# main.net
KiCad netlist of a schematic drawn in EAGLE
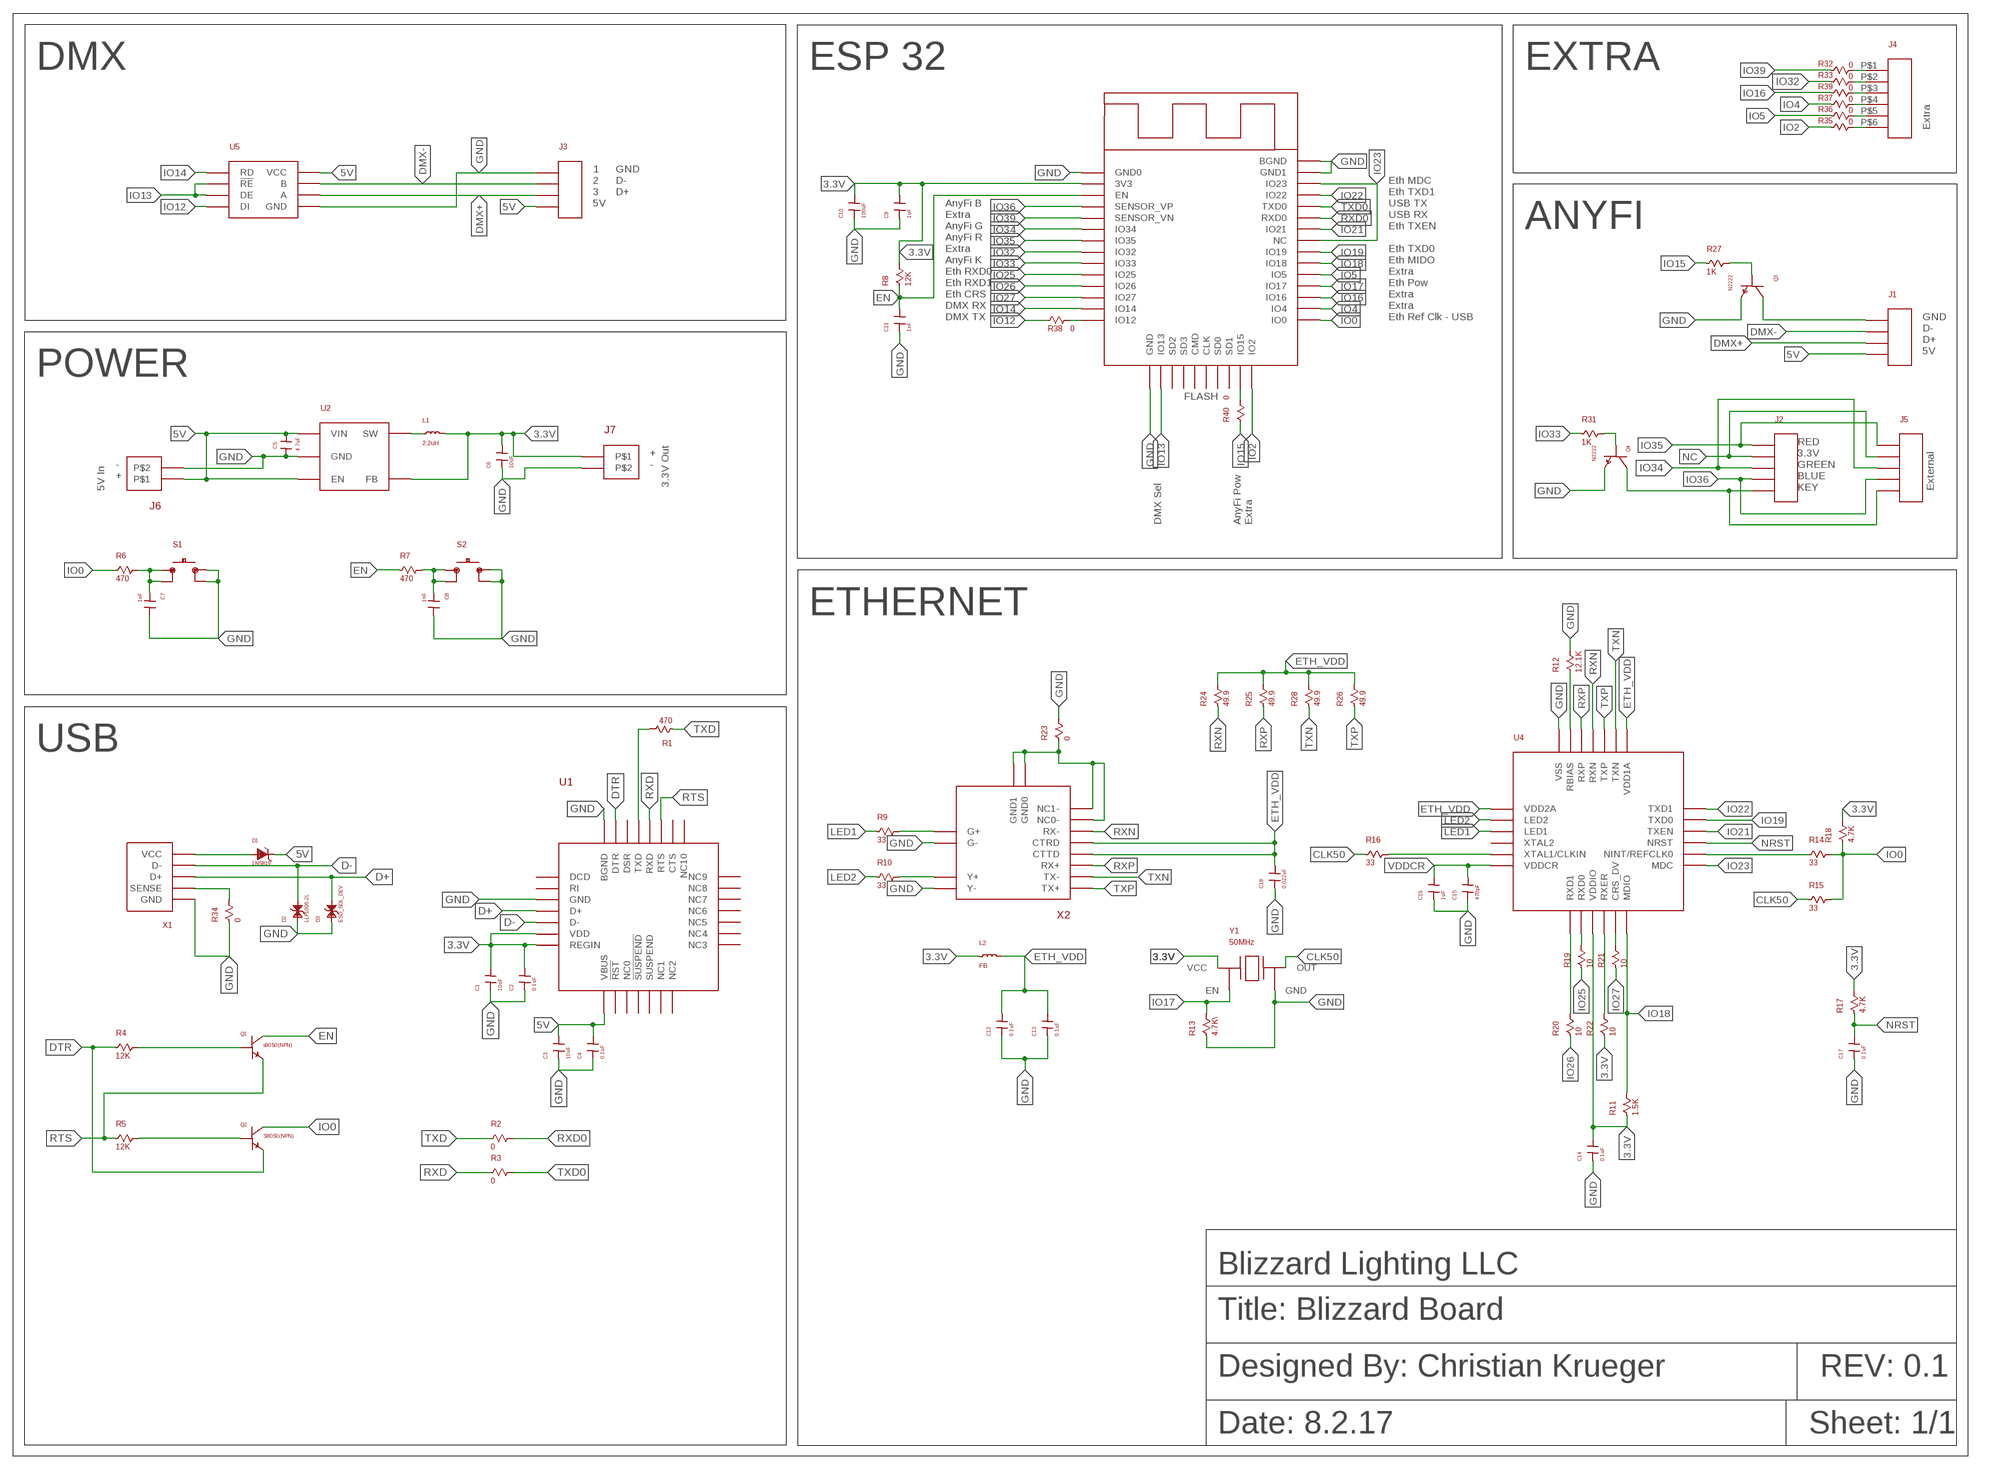
[diagram p0: schematic, sheet 1]

(export (version "E")
  (design (tool "Eeschema 10.0.6"))
  (components
    (comp (ref "C1")
      (value "10uF")
      (footprint "eagle-import:0805_PKG")
      (libsource (lib "eagle-import") (part "0805_CAP_DEV"))
    )
    (comp (ref "C2")
      (value "0.1uF")
      (footprint "eagle-import:0805_PKG")
      (libsource (lib "eagle-import") (part "0805_CAP_DEV"))
    )
    (comp (ref "C3")
      (value "10uF")
      (footprint "eagle-import:0805_PKG")
      (libsource (lib "eagle-import") (part "0805_CAP_DEV"))
    )
    (comp (ref "C4")
      (value "0.1uF")
      (footprint "eagle-import:0805_PKG")
      (libsource (lib "eagle-import") (part "0805_CAP_DEV"))
    )
    (comp (ref "C5")
      (value "4.7uF")
      (footprint "eagle-import:0805_PKG")
      (libsource (lib "eagle-import") (part "0805_CAP_DEV"))
    )
    (comp (ref "C6")
      (value "10uF")
      (footprint "eagle-import:0805_PKG")
      (libsource (lib "eagle-import") (part "0805_CAP_DEV"))
    )
    (comp (ref "C7")
      (value "1nF")
      (footprint "eagle-import:0805_PKG")
      (libsource (lib "eagle-import") (part "0805_CAP_DEV"))
    )
    (comp (ref "C8")
      (value "1nF")
      (footprint "eagle-import:0805_PKG")
      (libsource (lib "eagle-import") (part "0805_CAP_DEV"))
    )
    (comp (ref "C9")
      (value "1uF")
      (footprint "eagle-import:0805_PKG")
      (libsource (lib "eagle-import") (part "0805_CAP_DEV"))
    )
    (comp (ref "C10")
      (value "100uF")
      (footprint "eagle-import:0805_PKG")
      (libsource (lib "eagle-import") (part "0805_CAP_DEV"))
    )
    (comp (ref "C11")
      (value "1nF")
      (footprint "eagle-import:0805_PKG")
      (libsource (lib "eagle-import") (part "0805_CAP_DEV"))
    )
    (comp (ref "C12")
      (value "0.1uF")
      (footprint "eagle-import:0805_PKG")
      (libsource (lib "eagle-import") (part "0805_CAP_DEV"))
    )
    (comp (ref "C13")
      (value "0.1uF")
      (footprint "eagle-import:0805_PKG")
      (libsource (lib "eagle-import") (part "0805_CAP_DEV"))
    )
    (comp (ref "C14")
      (value "0.1uF")
      (footprint "eagle-import:0805_PKG")
      (libsource (lib "eagle-import") (part "0805_CAP_DEV"))
    )
    (comp (ref "C15")
      (value "470pF")
      (footprint "eagle-import:0805_PKG")
      (libsource (lib "eagle-import") (part "0805_CAP_DEV"))
    )
    (comp (ref "C16")
      (value "1uF")
      (footprint "eagle-import:0805_PKG")
      (libsource (lib "eagle-import") (part "0805_CAP_DEV"))
    )
    (comp (ref "C17")
      (value "0.1uF")
      (footprint "eagle-import:0805_PKG")
      (libsource (lib "eagle-import") (part "0805_CAP_DEV"))
    )
    (comp (ref "C18")
      (value "0.022uF")
      (footprint "eagle-import:0805_PKG")
      (libsource (lib "eagle-import") (part "0805_CAP_DEV"))
    )
    (comp (ref "D1")
      (value "1N5819")
      (footprint "eagle-import:ZENER_PKG")
      (libsource (lib "eagle-import") (part "ZENER_DEV"))
    )
    (comp (ref "D2")
      (value "LLP1006-2L")
      (footprint "eagle-import:ESD_SOL_PKG")
      (libsource (lib "eagle-import") (part "ESD_SOL_DEV"))
    )
    (comp (ref "D3")
      (value "ESD_SOL_DEV")
      (footprint "eagle-import:ESD_SOL_PKG")
      (libsource (lib "eagle-import") (part "ESD_SOL_DEV"))
    )
    (comp (ref "J1")
      (value "XH_4POS_DEV")
      (footprint "eagle-import:XH_4POS_PKG")
      (libsource (lib "eagle-import") (part "XH_4POS_DEV"))
    )
    (comp (ref "J2")
      (value "XH_5POS_DEV")
      (footprint "eagle-import:XH_5POS_PKG")
      (libsource (lib "eagle-import") (part "XH_5POS_DEV"))
    )
    (comp (ref "J3")
      (value "XH_4POS_DEV")
      (footprint "eagle-import:XH_4POS_PKG")
      (libsource (lib "eagle-import") (part "XH_4POS_DEV"))
    )
    (comp (ref "J4")
      (value "XH_6POS_DEV")
      (footprint "eagle-import:XH_6POS_PKG")
      (libsource (lib "eagle-import") (part "XH_6POS_DEV"))
    )
    (comp (ref "J5")
      (value "XH_5POS_DEV")
      (footprint "eagle-import:XH_5POS_PKG")
      (libsource (lib "eagle-import") (part "XH_5POS_DEV"))
    )
    (comp (ref "J6")
      (value "XH_2POS_DEV")
      (footprint "eagle-import:XH_2POS_PKG")
      (libsource (lib "eagle-import") (part "XH_2POS_DEV"))
    )
    (comp (ref "J7")
      (value "XH_2POS_DEV")
      (footprint "eagle-import:XH_2POS_PKG")
      (libsource (lib "eagle-import") (part "XH_2POS_DEV"))
    )
    (comp (ref "L1")
      (value "2.2uH")
      (footprint "eagle-import:0805_PKG")
      (libsource (lib "eagle-import") (part "0805_IND_DEV"))
    )
    (comp (ref "L2")
      (value "FB")
      (footprint "eagle-import:0805_PKG")
      (libsource (lib "eagle-import") (part "0805_IND_DEV"))
    )
    (comp (ref "Q1")
      (value "s8050(NPN)")
      (footprint "eagle-import:SOT_23_3_PKG")
      (libsource (lib "eagle-import") (part "NPN_1.5A_40V_DEV"))
    )
    (comp (ref "Q2")
      (value "S8050(NPN)")
      (footprint "eagle-import:SOT_23_3_PKG")
      (libsource (lib "eagle-import") (part "NPN_1.5A_40V_DEV"))
    )
    (comp (ref "Q3")
      (value "N2222")
      (footprint "eagle-import:SOT_23_3_PKG")
      (libsource (lib "eagle-import") (part "NPN_N2222_DEV"))
    )
    (comp (ref "Q4")
      (value "N2222")
      (footprint "eagle-import:SOT_23_3_PKG")
      (libsource (lib "eagle-import") (part "NPN_N2222_DEV"))
    )
    (comp (ref "R1")
      (value "470")
      (footprint "eagle-import:0805_PKG")
      (libsource (lib "eagle-import") (part "0805_RES_DEV"))
    )
    (comp (ref "R2")
      (value "0")
      (footprint "eagle-import:0805_PKG")
      (libsource (lib "eagle-import") (part "0805_RES_DEV"))
    )
    (comp (ref "R3")
      (value "0")
      (footprint "eagle-import:0805_PKG")
      (libsource (lib "eagle-import") (part "0805_RES_DEV"))
    )
    (comp (ref "R4")
      (value "12K")
      (footprint "eagle-import:0805_PKG")
      (libsource (lib "eagle-import") (part "0805_RES_DEV"))
    )
    (comp (ref "R5")
      (value "12K")
      (footprint "eagle-import:0805_PKG")
      (libsource (lib "eagle-import") (part "0805_RES_DEV"))
    )
    (comp (ref "R6")
      (value "470")
      (footprint "eagle-import:0805_PKG")
      (libsource (lib "eagle-import") (part "0805_RES_DEV"))
    )
    (comp (ref "R7")
      (value "470")
      (footprint "eagle-import:0805_PKG")
      (libsource (lib "eagle-import") (part "0805_RES_DEV"))
    )
    (comp (ref "R8")
      (value "12K")
      (footprint "eagle-import:0805_PKG")
      (libsource (lib "eagle-import") (part "0805_RES_DEV"))
    )
    (comp (ref "R9")
      (value "33")
      (footprint "eagle-import:0805_PKG")
      (libsource (lib "eagle-import") (part "0805_RES_DEV"))
    )
    (comp (ref "R10")
      (value "33")
      (footprint "eagle-import:0805_PKG")
      (libsource (lib "eagle-import") (part "0805_RES_DEV"))
    )
    (comp (ref "R11")
      (value "1.5K")
      (footprint "eagle-import:0805_PKG")
      (libsource (lib "eagle-import") (part "0805_RES_DEV"))
    )
    (comp (ref "R12")
      (value "12.1K")
      (footprint "eagle-import:0805_PKG")
      (libsource (lib "eagle-import") (part "0805_RES_DEV"))
    )
    (comp (ref "R13")
      (value "4.7K\\")
      (footprint "eagle-import:0805_PKG")
      (libsource (lib "eagle-import") (part "0805_RES_DEV"))
    )
    (comp (ref "R14")
      (value "33")
      (footprint "eagle-import:0805_PKG")
      (libsource (lib "eagle-import") (part "0805_RES_DEV"))
    )
    (comp (ref "R15")
      (value "33")
      (footprint "eagle-import:0805_PKG")
      (libsource (lib "eagle-import") (part "0805_RES_DEV"))
    )
    (comp (ref "R16")
      (value "33")
      (footprint "eagle-import:0805_PKG")
      (libsource (lib "eagle-import") (part "0805_RES_DEV"))
    )
    (comp (ref "R17")
      (value "4.7K")
      (footprint "eagle-import:0805_PKG")
      (libsource (lib "eagle-import") (part "0805_RES_DEV"))
    )
    (comp (ref "R18")
      (value "4.7K")
      (footprint "eagle-import:0805_PKG")
      (libsource (lib "eagle-import") (part "0805_RES_DEV"))
    )
    (comp (ref "R19")
      (value "10")
      (footprint "eagle-import:0805_PKG")
      (libsource (lib "eagle-import") (part "0805_RES_DEV"))
    )
    (comp (ref "R20")
      (value "10")
      (footprint "eagle-import:0805_PKG")
      (libsource (lib "eagle-import") (part "0805_RES_DEV"))
    )
    (comp (ref "R21")
      (value "10")
      (footprint "eagle-import:0805_PKG")
      (libsource (lib "eagle-import") (part "0805_RES_DEV"))
    )
    (comp (ref "R22")
      (value "10")
      (footprint "eagle-import:0805_PKG")
      (libsource (lib "eagle-import") (part "0805_RES_DEV"))
    )
    (comp (ref "R23")
      (value "0")
      (footprint "eagle-import:0805_PKG")
      (libsource (lib "eagle-import") (part "0805_RES_DEV"))
    )
    (comp (ref "R24")
      (value "49.9")
      (footprint "eagle-import:0805_PKG")
      (libsource (lib "eagle-import") (part "0805_RES_DEV"))
    )
    (comp (ref "R25")
      (value "49.9")
      (footprint "eagle-import:0805_PKG")
      (libsource (lib "eagle-import") (part "0805_RES_DEV"))
    )
    (comp (ref "R26")
      (value "49.9")
      (footprint "eagle-import:0805_PKG")
      (libsource (lib "eagle-import") (part "0805_RES_DEV"))
    )
    (comp (ref "R27")
      (value "1K")
      (footprint "eagle-import:0805_PKG")
      (libsource (lib "eagle-import") (part "0805_RES_DEV"))
    )
    (comp (ref "R28")
      (value "49.9")
      (footprint "eagle-import:0805_PKG")
      (libsource (lib "eagle-import") (part "0805_RES_DEV"))
    )
    (comp (ref "R31")
      (value "1K")
      (footprint "eagle-import:0805_PKG")
      (libsource (lib "eagle-import") (part "0805_RES_DEV"))
    )
    (comp (ref "R32")
      (value "0")
      (footprint "eagle-import:0805_PKG")
      (libsource (lib "eagle-import") (part "0805_RES_DEV"))
    )
    (comp (ref "R33")
      (value "0")
      (footprint "eagle-import:0805_PKG")
      (libsource (lib "eagle-import") (part "0805_RES_DEV"))
    )
    (comp (ref "R34")
      (value "0")
      (footprint "eagle-import:0805_PKG")
      (libsource (lib "eagle-import") (part "0805_RES_DEV"))
    )
    (comp (ref "R35")
      (value "0")
      (footprint "eagle-import:0805_PKG")
      (libsource (lib "eagle-import") (part "0805_RES_DEV"))
    )
    (comp (ref "R36")
      (value "0")
      (footprint "eagle-import:0805_PKG")
      (libsource (lib "eagle-import") (part "0805_RES_DEV"))
    )
    (comp (ref "R37")
      (value "0")
      (footprint "eagle-import:0805_PKG")
      (libsource (lib "eagle-import") (part "0805_RES_DEV"))
    )
    (comp (ref "R38")
      (value "0")
      (footprint "eagle-import:0805_PKG")
      (libsource (lib "eagle-import") (part "0805_RES_DEV"))
    )
    (comp (ref "R39")
      (value "0")
      (footprint "eagle-import:0805_PKG")
      (libsource (lib "eagle-import") (part "0805_RES_DEV"))
    )
    (comp (ref "R40")
      (value "0")
      (footprint "eagle-import:0805_PKG")
      (libsource (lib "eagle-import") (part "0805_RES_DEV"))
    )
    (comp (ref "S1")
      (value "TACTILE_PB_DEV")
      (footprint "eagle-import:TACKTILE_PB_PKG")
      (libsource (lib "eagle-import") (part "TACTILE_PB_DEV"))
    )
    (comp (ref "S2")
      (value "TACTILE_PB_DEV")
      (footprint "eagle-import:TACKTILE_PB_PKG")
      (libsource (lib "eagle-import") (part "TACTILE_PB_DEV"))
    )
    (comp (ref "U1")
      (value "USB_TO_UART_DEV")
      (footprint "eagle-import:QFN_28_PKG")
      (libsource (lib "eagle-import") (part "USB_TO_UART_DEV"))
    )
    (comp (ref "U2")
      (value "BUCK_CONVERTER_DEV")
      (footprint "eagle-import:SOT_23_PKG")
      (libsource (lib "eagle-import") (part "BUCK_CONVERTER_DEV"))
    )
    (comp (ref "U3")
      (value "ESP_WROOM_32_DEV")
      (footprint "eagle-import:ESP_WROOM_32_PKG")
      (libsource (lib "eagle-import") (part "ESP_WROOM_32_DEV"))
    )
    (comp (ref "U4")
      (value "LAN8720_DEV")
      (footprint "eagle-import:QFN_24_PKG")
      (libsource (lib "eagle-import") (part "LAN8720_DEV"))
    )
    (comp (ref "U5")
      (value "MAX_485_DEV")
      (footprint "eagle-import:MAX_485_PKG")
      (libsource (lib "eagle-import") (part "MAX_485_DEV"))
    )
    (comp (ref "X1")
      (value "USB_CONN_DEV")
      (footprint "eagle-import:USB_CONN_PKG")
      (libsource (lib "eagle-import") (part "USB_CONN_DEV"))
    )
    (comp (ref "X2")
      (value "ETHERNET_DEV")
      (footprint "eagle-import:ETHERNET_PKG")
      (libsource (lib "eagle-import") (part "ETHERNET_DEV"))
    )
    (comp (ref "Y1")
      (value "50MHz")
      (footprint "eagle-import:OSC_PKG")
      (libsource (lib "eagle-import") (part "OSC_DEV"))
    )
  )
  (nets
    (net (code "1") (name "3.3V") (class "Default")
      (node (ref "C1") (pin "P$2") (pinfunction "P$2_P$2") (pintype "bidirectional"))
      (node (ref "C10") (pin "P$2") (pinfunction "P$2_P$2") (pintype "bidirectional"))
      (node (ref "C14") (pin "P$2") (pinfunction "P$2_P$2") (pintype "bidirectional"))
      (node (ref "C2") (pin "P$2") (pinfunction "P$2_P$2") (pintype "bidirectional"))
      (node (ref "C6") (pin "P$2") (pinfunction "P$2_P$2") (pintype "bidirectional"))
      (node (ref "C9") (pin "P$2") (pinfunction "P$2_P$2") (pintype "bidirectional"))
      (node (ref "J7") (pin "P$1") (pinfunction "P$1_P$1") (pintype "bidirectional"))
      (node (ref "L1") (pin "P$2") (pinfunction "P$2_P$2") (pintype "bidirectional"))
      (node (ref "L2") (pin "P$1") (pinfunction "P$1_P$1") (pintype "bidirectional"))
      (node (ref "R11") (pin "P$1") (pinfunction "P$1_P$1") (pintype "bidirectional"))
      (node (ref "R17") (pin "P$2") (pinfunction "P$2_P$2") (pintype "bidirectional"))
      (node (ref "R18") (pin "P$2") (pinfunction "P$2_P$2") (pintype "bidirectional"))
      (node (ref "R22") (pin "P$1") (pinfunction "P$1_P$1") (pintype "bidirectional"))
      (node (ref "R8") (pin "P$2") (pinfunction "P$2_P$2") (pintype "bidirectional"))
      (node (ref "U1") (pin "REGIN") (pinfunction "REGIN_REGIN") (pintype "bidirectional"))
      (node (ref "U1") (pin "VDD") (pinfunction "VDD_VDD") (pintype "bidirectional"))
      (node (ref "U2") (pin "4") (pinfunction "FB_4") (pintype "bidirectional"))
      (node (ref "U3") (pin "3V3") (pinfunction "3V3_3V3") (pintype "bidirectional"))
      (node (ref "U4") (pin "9") (pinfunction "VDDIO_9") (pintype "bidirectional"))
      (node (ref "Y1") (pin "4") (pinfunction "VCC_4") (pintype "bidirectional"))
    )
    (net (code "2") (name "5V") (class "Default")
      (node (ref "C3") (pin "P$2") (pinfunction "P$2_P$2") (pintype "bidirectional"))
      (node (ref "C4") (pin "P$2") (pinfunction "P$2_P$2") (pintype "bidirectional"))
      (node (ref "C5") (pin "P$2") (pinfunction "P$2_P$2") (pintype "bidirectional"))
      (node (ref "D1") (pin "P$2") (pinfunction "P$2_P$2") (pintype "bidirectional"))
      (node (ref "J1") (pin "P$4") (pinfunction "P$4_P$4") (pintype "bidirectional"))
      (node (ref "J3") (pin "P$4") (pinfunction "P$4_P$4") (pintype "bidirectional"))
      (node (ref "J6") (pin "P$1") (pinfunction "P$1_P$1") (pintype "bidirectional"))
      (node (ref "U1") (pin "VBUS") (pinfunction "VBUS_VBUS") (pintype "bidirectional"))
      (node (ref "U2") (pin "1") (pinfunction "VIN_1") (pintype "bidirectional"))
      (node (ref "U2") (pin "3") (pinfunction "EN_3") (pintype "bidirectional"))
      (node (ref "U5") (pin "P$8") (pinfunction "VCC_P$8") (pintype "bidirectional"))
    )
    (net (code "3") (name "CLK50") (class "Default")
      (node (ref "R15") (pin "P$1") (pinfunction "P$1_P$1") (pintype "bidirectional"))
      (node (ref "R16") (pin "P$1") (pinfunction "P$1_P$1") (pintype "bidirectional"))
      (node (ref "Y1") (pin "3") (pinfunction "OUT_3") (pintype "bidirectional"))
    )
    (net (code "4") (name "D+") (class "Default")
      (node (ref "D3") (pin "P$2") (pinfunction "P$2_P$2") (pintype "bidirectional"))
      (node (ref "U1") (pin "D+") (pinfunction "D+_D+") (pintype "bidirectional"))
      (node (ref "X1") (pin "PIN3") (pinfunction "D+_PIN3") (pintype "bidirectional"))
    )
    (net (code "5") (name "D-") (class "Default")
      (node (ref "D2") (pin "P$2") (pinfunction "P$2_P$2") (pintype "bidirectional"))
      (node (ref "U1") (pin "D-") (pinfunction "D-_D-") (pintype "bidirectional"))
      (node (ref "X1") (pin "PIN2") (pinfunction "D-_PIN2") (pintype "bidirectional"))
    )
    (net (code "6") (name "DMX+") (class "Default")
      (node (ref "J1") (pin "P$3") (pinfunction "P$3_P$3") (pintype "bidirectional"))
      (node (ref "J3") (pin "P$3") (pinfunction "P$3_P$3") (pintype "bidirectional"))
      (node (ref "U5") (pin "P$6") (pinfunction "A_P$6") (pintype "bidirectional"))
    )
    (net (code "7") (name "DMX-") (class "Default")
      (node (ref "J1") (pin "P$2") (pinfunction "P$2_P$2") (pintype "bidirectional"))
      (node (ref "J3") (pin "P$2") (pinfunction "P$2_P$2") (pintype "bidirectional"))
      (node (ref "U5") (pin "P$7") (pinfunction "B_P$7") (pintype "bidirectional"))
    )
    (net (code "8") (name "DTR") (class "Default")
      (node (ref "Q2") (pin "P$2") (pinfunction "E_P$2") (pintype "bidirectional"))
      (node (ref "R4") (pin "P$1") (pinfunction "P$1_P$1") (pintype "bidirectional"))
      (node (ref "U1") (pin "DTR") (pinfunction "DTR_DTR") (pintype "bidirectional"))
    )
    (net (code "9") (name "EN") (class "Default")
      (node (ref "C11") (pin "P$2") (pinfunction "P$2_P$2") (pintype "bidirectional"))
      (node (ref "Q1") (pin "P$3") (pinfunction "C_P$3") (pintype "bidirectional"))
      (node (ref "R7") (pin "P$1") (pinfunction "P$1_P$1") (pintype "bidirectional"))
      (node (ref "R8") (pin "P$1") (pinfunction "P$1_P$1") (pintype "bidirectional"))
      (node (ref "U3") (pin "EN") (pinfunction "EN_EN") (pintype "bidirectional"))
    )
    (net (code "10") (name "ETH_VDD") (class "Default")
      (node (ref "C12") (pin "P$2") (pinfunction "P$2_P$2") (pintype "bidirectional"))
      (node (ref "C13") (pin "P$2") (pinfunction "P$2_P$2") (pintype "bidirectional"))
      (node (ref "C18") (pin "P$2") (pinfunction "P$2_P$2") (pintype "bidirectional"))
      (node (ref "L2") (pin "P$2") (pinfunction "P$2_P$2") (pintype "bidirectional"))
      (node (ref "R24") (pin "P$2") (pinfunction "P$2_P$2") (pintype "bidirectional"))
      (node (ref "R25") (pin "P$2") (pinfunction "P$2_P$2") (pintype "bidirectional"))
      (node (ref "R26") (pin "P$2") (pinfunction "P$2_P$2") (pintype "bidirectional"))
      (node (ref "R28") (pin "P$2") (pinfunction "P$2_P$2") (pintype "bidirectional"))
      (node (ref "U4") (pin "1") (pinfunction "VDD2A_1") (pintype "bidirectional"))
      (node (ref "U4") (pin "19") (pinfunction "VDD1A_19") (pintype "bidirectional"))
      (node (ref "X2") (pin "4") (pinfunction "CTTD_4") (pintype "bidirectional"))
      (node (ref "X2") (pin "5") (pinfunction "CTRD_5") (pintype "bidirectional"))
    )
    (net (code "11") (name "GND") (class "Default")
      (node (ref "C1") (pin "P$1") (pinfunction "P$1_P$1") (pintype "bidirectional"))
      (node (ref "C10") (pin "P$1") (pinfunction "P$1_P$1") (pintype "bidirectional"))
      (node (ref "C11") (pin "P$1") (pinfunction "P$1_P$1") (pintype "bidirectional"))
      (node (ref "C12") (pin "P$1") (pinfunction "P$1_P$1") (pintype "bidirectional"))
      (node (ref "C13") (pin "P$1") (pinfunction "P$1_P$1") (pintype "bidirectional"))
      (node (ref "C14") (pin "P$1") (pinfunction "P$1_P$1") (pintype "bidirectional"))
      (node (ref "C15") (pin "P$1") (pinfunction "P$1_P$1") (pintype "bidirectional"))
      (node (ref "C16") (pin "P$1") (pinfunction "P$1_P$1") (pintype "bidirectional"))
      (node (ref "C17") (pin "P$1") (pinfunction "P$1_P$1") (pintype "bidirectional"))
      (node (ref "C18") (pin "P$1") (pinfunction "P$1_P$1") (pintype "bidirectional"))
      (node (ref "C2") (pin "P$1") (pinfunction "P$1_P$1") (pintype "bidirectional"))
      (node (ref "C3") (pin "P$1") (pinfunction "P$1_P$1") (pintype "bidirectional"))
      (node (ref "C4") (pin "P$1") (pinfunction "P$1_P$1") (pintype "bidirectional"))
      (node (ref "C5") (pin "P$1") (pinfunction "P$1_P$1") (pintype "bidirectional"))
      (node (ref "C6") (pin "P$1") (pinfunction "P$1_P$1") (pintype "bidirectional"))
      (node (ref "C7") (pin "P$2") (pinfunction "P$2_P$2") (pintype "bidirectional"))
      (node (ref "C8") (pin "P$2") (pinfunction "P$2_P$2") (pintype "bidirectional"))
      (node (ref "C9") (pin "P$1") (pinfunction "P$1_P$1") (pintype "bidirectional"))
      (node (ref "D2") (pin "P$1") (pinfunction "P$1_P$1") (pintype "bidirectional"))
      (node (ref "D3") (pin "P$1") (pinfunction "P$1_P$1") (pintype "bidirectional"))
      (node (ref "J3") (pin "P$1") (pinfunction "P$1_P$1") (pintype "bidirectional"))
      (node (ref "J6") (pin "P$2") (pinfunction "P$2_P$2") (pintype "bidirectional"))
      (node (ref "J7") (pin "P$2") (pinfunction "P$2_P$2") (pintype "bidirectional"))
      (node (ref "Q3") (pin "P$2") (pinfunction "E_P$2") (pintype "bidirectional"))
      (node (ref "Q4") (pin "P$2") (pinfunction "E_P$2") (pintype "bidirectional"))
      (node (ref "R12") (pin "P$2") (pinfunction "P$2_P$2") (pintype "bidirectional"))
      (node (ref "R13") (pin "P$1") (pinfunction "P$1_P$1") (pintype "bidirectional"))
      (node (ref "R23") (pin "P$2") (pinfunction "P$2_P$2") (pintype "bidirectional"))
      (node (ref "R34") (pin "P$2") (pinfunction "P$2_P$2") (pintype "bidirectional"))
      (node (ref "S1") (pin "3") (pinfunction "3_3") (pintype "bidirectional"))
      (node (ref "S1") (pin "4") (pinfunction "4_4") (pintype "bidirectional"))
      (node (ref "S2") (pin "3") (pinfunction "3_3") (pintype "bidirectional"))
      (node (ref "S2") (pin "4") (pinfunction "4_4") (pintype "bidirectional"))
      (node (ref "U1") (pin "BGND") (pinfunction "BGND_BGND") (pintype "bidirectional"))
      (node (ref "U1") (pin "GND") (pinfunction "GND_GND") (pintype "bidirectional"))
      (node (ref "U2") (pin "2") (pinfunction "GND_2") (pintype "bidirectional"))
      (node (ref "U3") (pin "BGND") (pinfunction "BGND_BGND") (pintype "bidirectional"))
      (node (ref "U3") (pin "GND0") (pinfunction "GND_GND0") (pintype "bidirectional"))
      (node (ref "U3") (pin "GND1") (pinfunction "GND0_GND1") (pintype "bidirectional"))
      (node (ref "U3") (pin "GND2") (pinfunction "GND1_GND2") (pintype "bidirectional"))
      (node (ref "U4") (pin "BGND") (pinfunction "VSS_BGND") (pintype "bidirectional"))
      (node (ref "U5") (pin "P$5") (pinfunction "GND_P$5") (pintype "bidirectional"))
      (node (ref "X1") (pin "PIN4") (pinfunction "SENSE_PIN4") (pintype "bidirectional"))
      (node (ref "X2") (pin "G-") (pinfunction "G-_G-") (pintype "bidirectional"))
      (node (ref "X2") (pin "Y-") (pinfunction "Y-_Y-") (pintype "bidirectional"))
      (node (ref "Y1") (pin "2") (pinfunction "GND_2") (pintype "bidirectional"))
    )
    (net (code "12") (name "IO0") (class "Default")
      (node (ref "Q2") (pin "P$3") (pinfunction "C_P$3") (pintype "bidirectional"))
      (node (ref "R14") (pin "P$2") (pinfunction "P$2_P$2") (pintype "bidirectional"))
      (node (ref "R15") (pin "P$2") (pinfunction "P$2_P$2") (pintype "bidirectional"))
      (node (ref "R18") (pin "P$1") (pinfunction "P$1_P$1") (pintype "bidirectional"))
      (node (ref "R6") (pin "P$1") (pinfunction "P$1_P$1") (pintype "bidirectional"))
      (node (ref "U3") (pin "IO0") (pinfunction "IO0_IO0") (pintype "bidirectional"))
    )
    (net (code "13") (name "IO2") (class "Default")
      (node (ref "R35") (pin "P$1") (pinfunction "P$1_P$1") (pintype "bidirectional"))
      (node (ref "U3") (pin "IO2") (pinfunction "IO2_IO2") (pintype "bidirectional"))
    )
    (net (code "14") (name "IO4") (class "Default")
      (node (ref "R37") (pin "P$1") (pinfunction "P$1_P$1") (pintype "bidirectional"))
      (node (ref "U3") (pin "IO4") (pinfunction "IO4_IO4") (pintype "bidirectional"))
    )
    (net (code "15") (name "IO5") (class "Default")
      (node (ref "R36") (pin "P$1") (pinfunction "P$1_P$1") (pintype "bidirectional"))
      (node (ref "U3") (pin "IO5") (pinfunction "IO5_IO5") (pintype "bidirectional"))
    )
    (net (code "16") (name "IO12") (class "Default")
      (node (ref "R38") (pin "P$1") (pinfunction "P$1_P$1") (pintype "bidirectional"))
      (node (ref "U5") (pin "P$4") (pinfunction "DI_P$4") (pintype "bidirectional"))
    )
    (net (code "17") (name "IO13") (class "Default")
      (node (ref "U3") (pin "IO13") (pinfunction "IO13_IO13") (pintype "bidirectional"))
      (node (ref "U5") (pin "P$2") (pinfunction "~{RE}_P$2") (pintype "bidirectional"))
      (node (ref "U5") (pin "P$3") (pinfunction "DE_P$3") (pintype "bidirectional"))
    )
    (net (code "18") (name "IO14") (class "Default")
      (node (ref "U3") (pin "IO14") (pinfunction "IO14_IO14") (pintype "bidirectional"))
      (node (ref "U5") (pin "P$1") (pinfunction "RD_P$1") (pintype "bidirectional"))
    )
    (net (code "19") (name "IO15") (class "Default")
      (node (ref "R27") (pin "P$1") (pinfunction "P$1_P$1") (pintype "bidirectional"))
      (node (ref "R40") (pin "P$1") (pinfunction "P$1_P$1") (pintype "bidirectional"))
    )
    (net (code "20") (name "IO16") (class "Default")
      (node (ref "R39") (pin "P$1") (pinfunction "P$1_P$1") (pintype "bidirectional"))
      (node (ref "U3") (pin "IO16") (pinfunction "IO16_IO16") (pintype "bidirectional"))
    )
    (net (code "21") (name "IO17") (class "Default")
      (node (ref "R13") (pin "P$2") (pinfunction "P$2_P$2") (pintype "bidirectional"))
      (node (ref "U3") (pin "IO17") (pinfunction "IO17_IO17") (pintype "bidirectional"))
      (node (ref "Y1") (pin "1") (pinfunction "EN_1") (pintype "bidirectional"))
    )
    (net (code "22") (name "IO18") (class "Default")
      (node (ref "R11") (pin "P$2") (pinfunction "P$2_P$2") (pintype "bidirectional"))
      (node (ref "U3") (pin "IO18") (pinfunction "IO18_IO18") (pintype "bidirectional"))
      (node (ref "U4") (pin "12") (pinfunction "MDIO_12") (pintype "bidirectional"))
    )
    (net (code "23") (name "IO19") (class "Default")
      (node (ref "U3") (pin "IO19") (pinfunction "IO19_IO19") (pintype "bidirectional"))
      (node (ref "U4") (pin "17") (pinfunction "TXD0_17") (pintype "bidirectional"))
    )
    (net (code "24") (name "IO21") (class "Default")
      (node (ref "U3") (pin "IO21") (pinfunction "IO21_IO21") (pintype "bidirectional"))
      (node (ref "U4") (pin "16") (pinfunction "TXEN_16") (pintype "bidirectional"))
    )
    (net (code "25") (name "IO22") (class "Default")
      (node (ref "U3") (pin "IO22") (pinfunction "IO22_IO22") (pintype "bidirectional"))
      (node (ref "U4") (pin "18") (pinfunction "TXD1_18") (pintype "bidirectional"))
    )
    (net (code "26") (name "IO23") (class "Default")
      (node (ref "U3") (pin "IO23") (pinfunction "IO23_IO23") (pintype "bidirectional"))
      (node (ref "U3") (pin "NC") (pinfunction "NC_NC") (pintype "bidirectional"))
      (node (ref "U4") (pin "13") (pinfunction "MDC_13") (pintype "bidirectional"))
    )
    (net (code "27") (name "IO25") (class "Default")
      (node (ref "R19") (pin "P$1") (pinfunction "P$1_P$1") (pintype "bidirectional"))
      (node (ref "U3") (pin "IO25") (pinfunction "IO25_IO25") (pintype "bidirectional"))
    )
    (net (code "28") (name "IO26") (class "Default")
      (node (ref "R20") (pin "P$1") (pinfunction "P$1_P$1") (pintype "bidirectional"))
      (node (ref "U3") (pin "IO26") (pinfunction "IO26_IO26") (pintype "bidirectional"))
    )
    (net (code "29") (name "IO27") (class "Default")
      (node (ref "R21") (pin "P$1") (pinfunction "P$1_P$1") (pintype "bidirectional"))
      (node (ref "U3") (pin "IO27") (pinfunction "IO27_IO27") (pintype "bidirectional"))
    )
    (net (code "30") (name "IO32") (class "Default")
      (node (ref "R33") (pin "P$1") (pinfunction "P$1_P$1") (pintype "bidirectional"))
      (node (ref "U3") (pin "IO32") (pinfunction "IO32_IO32") (pintype "bidirectional"))
    )
    (net (code "31") (name "IO33") (class "Default")
      (node (ref "R31") (pin "P$1") (pinfunction "P$1_P$1") (pintype "bidirectional"))
      (node (ref "U3") (pin "IO33") (pinfunction "IO33_IO33") (pintype "bidirectional"))
    )
    (net (code "32") (name "IO34") (class "Default")
      (node (ref "J2") (pin "P$3") (pinfunction "P$3_P$3") (pintype "bidirectional"))
      (node (ref "J5") (pin "P$3") (pinfunction "P$3_P$3") (pintype "bidirectional"))
      (node (ref "U3") (pin "IO34") (pinfunction "IO34_IO34") (pintype "bidirectional"))
    )
    (net (code "33") (name "IO35") (class "Default")
      (node (ref "J2") (pin "P$1") (pinfunction "P$1_P$1") (pintype "bidirectional"))
      (node (ref "J5") (pin "P$1") (pinfunction "P$1_P$1") (pintype "bidirectional"))
      (node (ref "U3") (pin "IO35") (pinfunction "IO35_IO35") (pintype "bidirectional"))
    )
    (net (code "34") (name "IO36") (class "Default")
      (node (ref "J2") (pin "P$4") (pinfunction "P$4_P$4") (pintype "bidirectional"))
      (node (ref "J5") (pin "P$4") (pinfunction "P$4_P$4") (pintype "bidirectional"))
      (node (ref "U3") (pin "SENSOR_VP") (pinfunction "SENSOR_VP_SENSOR_VP") (pintype "bidirectional"))
    )
    (net (code "35") (name "IO39") (class "Default")
      (node (ref "R32") (pin "P$1") (pinfunction "P$1_P$1") (pintype "bidirectional"))
      (node (ref "U3") (pin "SENSOR_VN") (pinfunction "SENSOR_VN_SENSOR_VN") (pintype "bidirectional"))
    )
    (net (code "36") (name "LED1") (class "Default")
      (node (ref "R9") (pin "P$1") (pinfunction "P$1_P$1") (pintype "bidirectional"))
      (node (ref "U4") (pin "3") (pinfunction "LED1_3") (pintype "bidirectional"))
    )
    (net (code "37") (name "LED2") (class "Default")
      (node (ref "R10") (pin "P$1") (pinfunction "P$1_P$1") (pintype "bidirectional"))
      (node (ref "U4") (pin "2") (pinfunction "LED2_2") (pintype "bidirectional"))
    )
    (net (code "38") (name "NC") (class "Default")
      (node (ref "J2") (pin "P$2") (pinfunction "P$2_P$2") (pintype "bidirectional"))
      (node (ref "J5") (pin "P$2") (pinfunction "P$2_P$2") (pintype "bidirectional"))
    )
    (net (code "39") (name "NRST") (class "Default")
      (node (ref "C17") (pin "P$2") (pinfunction "P$2_P$2") (pintype "bidirectional"))
      (node (ref "R17") (pin "P$1") (pinfunction "P$1_P$1") (pintype "bidirectional"))
      (node (ref "U4") (pin "15") (pinfunction "NRST_15") (pintype "bidirectional"))
    )
    (net (code "40") (name "Net-(C7-PadP$1)") (class "Default")
      (node (ref "C7") (pin "P$1") (pinfunction "P$1_P$1") (pintype "bidirectional"))
      (node (ref "R6") (pin "P$2") (pinfunction "P$2_P$2") (pintype "bidirectional"))
      (node (ref "S1") (pin "1") (pinfunction "1_1") (pintype "bidirectional"))
      (node (ref "S1") (pin "2") (pinfunction "2_2") (pintype "bidirectional"))
    )
    (net (code "41") (name "Net-(C8-PadP$1)") (class "Default")
      (node (ref "C8") (pin "P$1") (pinfunction "P$1_P$1") (pintype "bidirectional"))
      (node (ref "R7") (pin "P$2") (pinfunction "P$2_P$2") (pintype "bidirectional"))
      (node (ref "S2") (pin "1") (pinfunction "1_1") (pintype "bidirectional"))
      (node (ref "S2") (pin "2") (pinfunction "2_2") (pintype "bidirectional"))
    )
    (net (code "42") (name "Net-(J4-PadP$1)") (class "Default")
      (node (ref "J4") (pin "P$1") (pinfunction "P$1_P$1") (pintype "bidirectional"))
      (node (ref "R32") (pin "P$2") (pinfunction "P$2_P$2") (pintype "bidirectional"))
    )
    (net (code "43") (name "Net-(J4-PadP$2)") (class "Default")
      (node (ref "J4") (pin "P$2") (pinfunction "P$2_P$2") (pintype "bidirectional"))
      (node (ref "R33") (pin "P$2") (pinfunction "P$2_P$2") (pintype "bidirectional"))
    )
    (net (code "44") (name "Net-(J4-PadP$3)") (class "Default")
      (node (ref "J4") (pin "P$3") (pinfunction "P$3_P$3") (pintype "bidirectional"))
      (node (ref "R39") (pin "P$2") (pinfunction "P$2_P$2") (pintype "bidirectional"))
    )
    (net (code "45") (name "Net-(J4-PadP$4)") (class "Default")
      (node (ref "J4") (pin "P$4") (pinfunction "P$4_P$4") (pintype "bidirectional"))
      (node (ref "R37") (pin "P$2") (pinfunction "P$2_P$2") (pintype "bidirectional"))
    )
    (net (code "46") (name "Net-(J4-PadP$5)") (class "Default")
      (node (ref "J4") (pin "P$5") (pinfunction "P$5_P$5") (pintype "bidirectional"))
      (node (ref "R36") (pin "P$2") (pinfunction "P$2_P$2") (pintype "bidirectional"))
    )
    (net (code "47") (name "Net-(J4-PadP$6)") (class "Default")
      (node (ref "J4") (pin "P$6") (pinfunction "P$6_P$6") (pintype "bidirectional"))
      (node (ref "R35") (pin "P$2") (pinfunction "P$2_P$2") (pintype "bidirectional"))
    )
    (net (code "48") (name "Net-(Q1-B)") (class "Default")
      (node (ref "Q1") (pin "P$1") (pinfunction "B_P$1") (pintype "bidirectional"))
      (node (ref "R4") (pin "P$2") (pinfunction "P$2_P$2") (pintype "bidirectional"))
    )
    (net (code "49") (name "Net-(Q2-B)") (class "Default")
      (node (ref "Q2") (pin "P$1") (pinfunction "B_P$1") (pintype "bidirectional"))
      (node (ref "R5") (pin "P$2") (pinfunction "P$2_P$2") (pintype "bidirectional"))
    )
    (net (code "50") (name "Net-(Q3-B)") (class "Default")
      (node (ref "Q3") (pin "P$1") (pinfunction "B_P$1") (pintype "bidirectional"))
      (node (ref "R27") (pin "P$2") (pinfunction "P$2_P$2") (pintype "bidirectional"))
    )
    (net (code "51") (name "Net-(Q3-C)") (class "Default")
      (node (ref "J1") (pin "P$1") (pinfunction "P$1_P$1") (pintype "bidirectional"))
      (node (ref "Q3") (pin "P$3") (pinfunction "C_P$3") (pintype "bidirectional"))
    )
    (net (code "52") (name "Net-(Q4-B)") (class "Default")
      (node (ref "Q4") (pin "P$1") (pinfunction "B_P$1") (pintype "bidirectional"))
      (node (ref "R31") (pin "P$2") (pinfunction "P$2_P$2") (pintype "bidirectional"))
    )
    (net (code "53") (name "Net-(Q4-C)") (class "Default")
      (node (ref "J2") (pin "P$5") (pinfunction "P$5_P$5") (pintype "bidirectional"))
      (node (ref "J5") (pin "P$5") (pinfunction "P$5_P$5") (pintype "bidirectional"))
      (node (ref "Q4") (pin "P$3") (pinfunction "C_P$3") (pintype "bidirectional"))
    )
    (net (code "54") (name "Net-(R1-PadP$2)") (class "Default")
      (node (ref "R1") (pin "P$2") (pinfunction "P$2_P$2") (pintype "bidirectional"))
      (node (ref "U1") (pin "TXD") (pinfunction "TXD_TXD") (pintype "bidirectional"))
    )
    (net (code "55") (name "Net-(R9-PadP$2)") (class "Default")
      (node (ref "R9") (pin "P$2") (pinfunction "P$2_P$2") (pintype "bidirectional"))
      (node (ref "X2") (pin "G+") (pinfunction "G+_G+") (pintype "bidirectional"))
    )
    (net (code "56") (name "Net-(R10-PadP$2)") (class "Default")
      (node (ref "R10") (pin "P$2") (pinfunction "P$2_P$2") (pintype "bidirectional"))
      (node (ref "X2") (pin "Y+") (pinfunction "Y+_Y+") (pintype "bidirectional"))
    )
    (net (code "57") (name "Net-(R38-PadP$2)") (class "Default")
      (node (ref "R38") (pin "P$2") (pinfunction "P$2_P$2") (pintype "bidirectional"))
      (node (ref "U3") (pin "IO12") (pinfunction "IO12_IO12") (pintype "bidirectional"))
    )
    (net (code "58") (name "Net-(R40-PadP$2)") (class "Default")
      (node (ref "R40") (pin "P$2") (pinfunction "P$2_P$2") (pintype "bidirectional"))
      (node (ref "U3") (pin "IO15") (pinfunction "IO15_IO15") (pintype "bidirectional"))
    )
    (net (code "59") (name "Net-(U2-SW)") (class "Default")
      (node (ref "L1") (pin "P$1") (pinfunction "P$1_P$1") (pintype "bidirectional"))
      (node (ref "U2") (pin "5") (pinfunction "SW_5") (pintype "bidirectional"))
    )
    (net (code "60") (name "Net-(U4-CRS_DV)") (class "Default")
      (node (ref "R21") (pin "P$2") (pinfunction "P$2_P$2") (pintype "bidirectional"))
      (node (ref "U4") (pin "11") (pinfunction "CRS_DV_11") (pintype "bidirectional"))
    )
    (net (code "61") (name "Net-(U4-NINT{slash}REFCLK0)") (class "Default")
      (node (ref "R14") (pin "P$1") (pinfunction "P$1_P$1") (pintype "bidirectional"))
      (node (ref "U4") (pin "14") (pinfunction "NINT/REFCLK0_14") (pintype "bidirectional"))
    )
    (net (code "62") (name "Net-(U4-RBIAS)") (class "Default")
      (node (ref "R12") (pin "P$1") (pinfunction "P$1_P$1") (pintype "bidirectional"))
      (node (ref "U4") (pin "24") (pinfunction "RBIAS_24") (pintype "bidirectional"))
    )
    (net (code "63") (name "Net-(U4-RXD0)") (class "Default")
      (node (ref "R19") (pin "P$2") (pinfunction "P$2_P$2") (pintype "bidirectional"))
      (node (ref "U4") (pin "8") (pinfunction "RXD0_8") (pintype "bidirectional"))
    )
    (net (code "64") (name "Net-(U4-RXD1)") (class "Default")
      (node (ref "R20") (pin "P$2") (pinfunction "P$2_P$2") (pintype "bidirectional"))
      (node (ref "U4") (pin "7") (pinfunction "RXD1_7") (pintype "bidirectional"))
    )
    (net (code "65") (name "Net-(U4-RXER)") (class "Default")
      (node (ref "R22") (pin "P$2") (pinfunction "P$2_P$2") (pintype "bidirectional"))
      (node (ref "U4") (pin "10") (pinfunction "RXER_10") (pintype "bidirectional"))
    )
    (net (code "66") (name "Net-(U4-XTAL1{slash}CLKIN)") (class "Default")
      (node (ref "R16") (pin "P$2") (pinfunction "P$2_P$2") (pintype "bidirectional"))
      (node (ref "U4") (pin "5") (pinfunction "XTAL1/CLKIN_5") (pintype "bidirectional"))
    )
    (net (code "67") (name "Net-(X1-GND)") (class "Default")
      (node (ref "R34") (pin "P$1") (pinfunction "P$1_P$1") (pintype "bidirectional"))
      (node (ref "X1") (pin "PIN5") (pinfunction "GND_PIN5") (pintype "bidirectional"))
    )
    (net (code "68") (name "Net-(X1-VCC)") (class "Default")
      (node (ref "D1") (pin "P$1") (pinfunction "P$1_P$1") (pintype "bidirectional"))
      (node (ref "X1") (pin "PIN1") (pinfunction "VCC_PIN1") (pintype "bidirectional"))
    )
    (net (code "69") (name "Net-(X2-NC0-)") (class "Default")
      (node (ref "R23") (pin "P$1") (pinfunction "P$1_P$1") (pintype "bidirectional"))
      (node (ref "X2") (pin "7") (pinfunction "NC0-_7") (pintype "bidirectional"))
      (node (ref "X2") (pin "8") (pinfunction "NC1-_8") (pintype "bidirectional"))
      (node (ref "X2") (pin "GND0") (pinfunction "GND0_GND0") (pintype "bidirectional"))
      (node (ref "X2") (pin "GND1") (pinfunction "GND1_GND1") (pintype "bidirectional"))
    )
    (net (code "70") (name "RTS") (class "Default")
      (node (ref "Q1") (pin "P$2") (pinfunction "E_P$2") (pintype "bidirectional"))
      (node (ref "R5") (pin "P$1") (pinfunction "P$1_P$1") (pintype "bidirectional"))
      (node (ref "U1") (pin "RTS") (pinfunction "RTS_RTS") (pintype "bidirectional"))
    )
    (net (code "71") (name "RXD") (class "Default")
      (node (ref "R3") (pin "P$1") (pinfunction "P$1_P$1") (pintype "bidirectional"))
      (node (ref "U1") (pin "RXD") (pinfunction "RXD_RXD") (pintype "bidirectional"))
    )
    (net (code "72") (name "RXD0") (class "Default")
      (node (ref "R2") (pin "P$2") (pinfunction "P$2_P$2") (pintype "bidirectional"))
      (node (ref "U3") (pin "RXD0") (pinfunction "RXD0_RXD0") (pintype "bidirectional"))
    )
    (net (code "73") (name "RXN") (class "Default")
      (node (ref "R24") (pin "P$1") (pinfunction "P$1_P$1") (pintype "bidirectional"))
      (node (ref "U4") (pin "22") (pinfunction "RXN_22") (pintype "bidirectional"))
      (node (ref "X2") (pin "6") (pinfunction "RX-_6") (pintype "bidirectional"))
    )
    (net (code "74") (name "RXP") (class "Default")
      (node (ref "R25") (pin "P$1") (pinfunction "P$1_P$1") (pintype "bidirectional"))
      (node (ref "U4") (pin "23") (pinfunction "RXP_23") (pintype "bidirectional"))
      (node (ref "X2") (pin "3") (pinfunction "RX+_3") (pintype "bidirectional"))
    )
    (net (code "75") (name "TXD") (class "Default")
      (node (ref "R1") (pin "P$1") (pinfunction "P$1_P$1") (pintype "bidirectional"))
      (node (ref "R2") (pin "P$1") (pinfunction "P$1_P$1") (pintype "bidirectional"))
    )
    (net (code "76") (name "TXD0") (class "Default")
      (node (ref "R3") (pin "P$2") (pinfunction "P$2_P$2") (pintype "bidirectional"))
      (node (ref "U3") (pin "TXD0") (pinfunction "TXD0_TXD0") (pintype "bidirectional"))
    )
    (net (code "77") (name "TXN") (class "Default")
      (node (ref "R28") (pin "P$1") (pinfunction "P$1_P$1") (pintype "bidirectional"))
      (node (ref "U4") (pin "20") (pinfunction "TXN_20") (pintype "bidirectional"))
      (node (ref "X2") (pin "2") (pinfunction "TX-_2") (pintype "bidirectional"))
    )
    (net (code "78") (name "TXP") (class "Default")
      (node (ref "R26") (pin "P$1") (pinfunction "P$1_P$1") (pintype "bidirectional"))
      (node (ref "U4") (pin "21") (pinfunction "TXP_21") (pintype "bidirectional"))
      (node (ref "X2") (pin "1") (pinfunction "TX+_1") (pintype "bidirectional"))
    )
    (net (code "79") (name "VDDCR") (class "Default")
      (node (ref "C15") (pin "P$2") (pinfunction "P$2_P$2") (pintype "bidirectional"))
      (node (ref "C16") (pin "P$2") (pinfunction "P$2_P$2") (pintype "bidirectional"))
      (node (ref "U4") (pin "6") (pinfunction "VDDCR_6") (pintype "bidirectional"))
    )
    (net (code "80") (name "unconnected-(U1-PadCTS)") (class "Default")
      (node (ref "U1") (pin "CTS") (pinfunction "CTS_CTS") (pintype "bidirectional"))
    )
    (net (code "81") (name "unconnected-(U1-PadDCD)") (class "Default")
      (node (ref "U1") (pin "DCD") (pinfunction "DCD_DCD") (pintype "bidirectional"))
    )
    (net (code "82") (name "unconnected-(U1-PadDSR)") (class "Default")
      (node (ref "U1") (pin "DSR") (pinfunction "DSR_DSR") (pintype "bidirectional"))
    )
    (net (code "83") (name "unconnected-(U1-PadNC0)") (class "Default")
      (node (ref "U1") (pin "NC0") (pinfunction "NC0_NC0") (pintype "bidirectional"))
    )
    (net (code "84") (name "unconnected-(U1-PadNC1)") (class "Default")
      (node (ref "U1") (pin "NC1") (pinfunction "NC1_NC1") (pintype "bidirectional"))
    )
    (net (code "85") (name "unconnected-(U1-PadNC2)") (class "Default")
      (node (ref "U1") (pin "NC2") (pinfunction "NC2_NC2") (pintype "bidirectional"))
    )
    (net (code "86") (name "unconnected-(U1-PadNC3)") (class "Default")
      (node (ref "U1") (pin "NC3") (pinfunction "NC3_NC3") (pintype "bidirectional"))
    )
    (net (code "87") (name "unconnected-(U1-PadNC4)") (class "Default")
      (node (ref "U1") (pin "NC4") (pinfunction "NC4_NC4") (pintype "bidirectional"))
    )
    (net (code "88") (name "unconnected-(U1-PadNC5)") (class "Default")
      (node (ref "U1") (pin "NC5") (pinfunction "NC5_NC5") (pintype "bidirectional"))
    )
    (net (code "89") (name "unconnected-(U1-PadNC6)") (class "Default")
      (node (ref "U1") (pin "NC6") (pinfunction "NC6_NC6") (pintype "bidirectional"))
    )
    (net (code "90") (name "unconnected-(U1-PadNC7)") (class "Default")
      (node (ref "U1") (pin "NC7") (pinfunction "NC7_NC7") (pintype "bidirectional"))
    )
    (net (code "91") (name "unconnected-(U1-PadNC8)") (class "Default")
      (node (ref "U1") (pin "NC8") (pinfunction "NC8_NC8") (pintype "bidirectional"))
    )
    (net (code "92") (name "unconnected-(U1-PadNC9)") (class "Default")
      (node (ref "U1") (pin "NC9") (pinfunction "NC9_NC9") (pintype "bidirectional"))
    )
    (net (code "93") (name "unconnected-(U1-PadNC10)") (class "Default")
      (node (ref "U1") (pin "NC10") (pinfunction "NC10_NC10") (pintype "bidirectional"))
    )
    (net (code "94") (name "unconnected-(U1-PadRI)") (class "Default")
      (node (ref "U1") (pin "RI") (pinfunction "RI_RI") (pintype "bidirectional"))
    )
    (net (code "95") (name "unconnected-(U1-PadSUSPEND)") (class "Default")
      (node (ref "U1") (pin "SUSPEND") (pinfunction "SUSPEND_SUSPEND") (pintype "bidirectional"))
    )
    (net (code "96") (name "unconnected-(U1-~{RST}-Pad!RST)") (class "Default")
      (node (ref "U1") (pin "!RST") (pinfunction "~{RST}_!RST") (pintype "bidirectional"))
    )
    (net (code "97") (name "unconnected-(U1-~{SUSPEND}-Pad!SUSPEND)") (class "Default")
      (node (ref "U1") (pin "!SUSPEND") (pinfunction "~{SUSPEND}_!SUSPEND") (pintype "bidirectional"))
    )
    (net (code "98") (name "unconnected-(U3-PadCLK)") (class "Default")
      (node (ref "U3") (pin "CLK") (pinfunction "CLK_CLK") (pintype "bidirectional"))
    )
    (net (code "99") (name "unconnected-(U3-PadCMD)") (class "Default")
      (node (ref "U3") (pin "CMD") (pinfunction "CMD_CMD") (pintype "bidirectional"))
    )
    (net (code "100") (name "unconnected-(U3-PadSD0)") (class "Default")
      (node (ref "U3") (pin "SD0") (pinfunction "SD0_SD0") (pintype "bidirectional"))
    )
    (net (code "101") (name "unconnected-(U3-PadSD1)") (class "Default")
      (node (ref "U3") (pin "SD1") (pinfunction "SD1_SD1") (pintype "bidirectional"))
    )
    (net (code "102") (name "unconnected-(U3-PadSD2)") (class "Default")
      (node (ref "U3") (pin "SD2") (pinfunction "SD2_SD2") (pintype "bidirectional"))
    )
    (net (code "103") (name "unconnected-(U3-PadSD3)") (class "Default")
      (node (ref "U3") (pin "SD3") (pinfunction "SD3_SD3") (pintype "bidirectional"))
    )
    (net (code "104") (name "unconnected-(U4-XTAL2-Pad4)") (class "Default")
      (node (ref "U4") (pin "4") (pinfunction "XTAL2_4") (pintype "bidirectional"))
    )
  )
)
